# USB_keyholder.net
KiCad netlist of a schematic drawn in Altium Designer
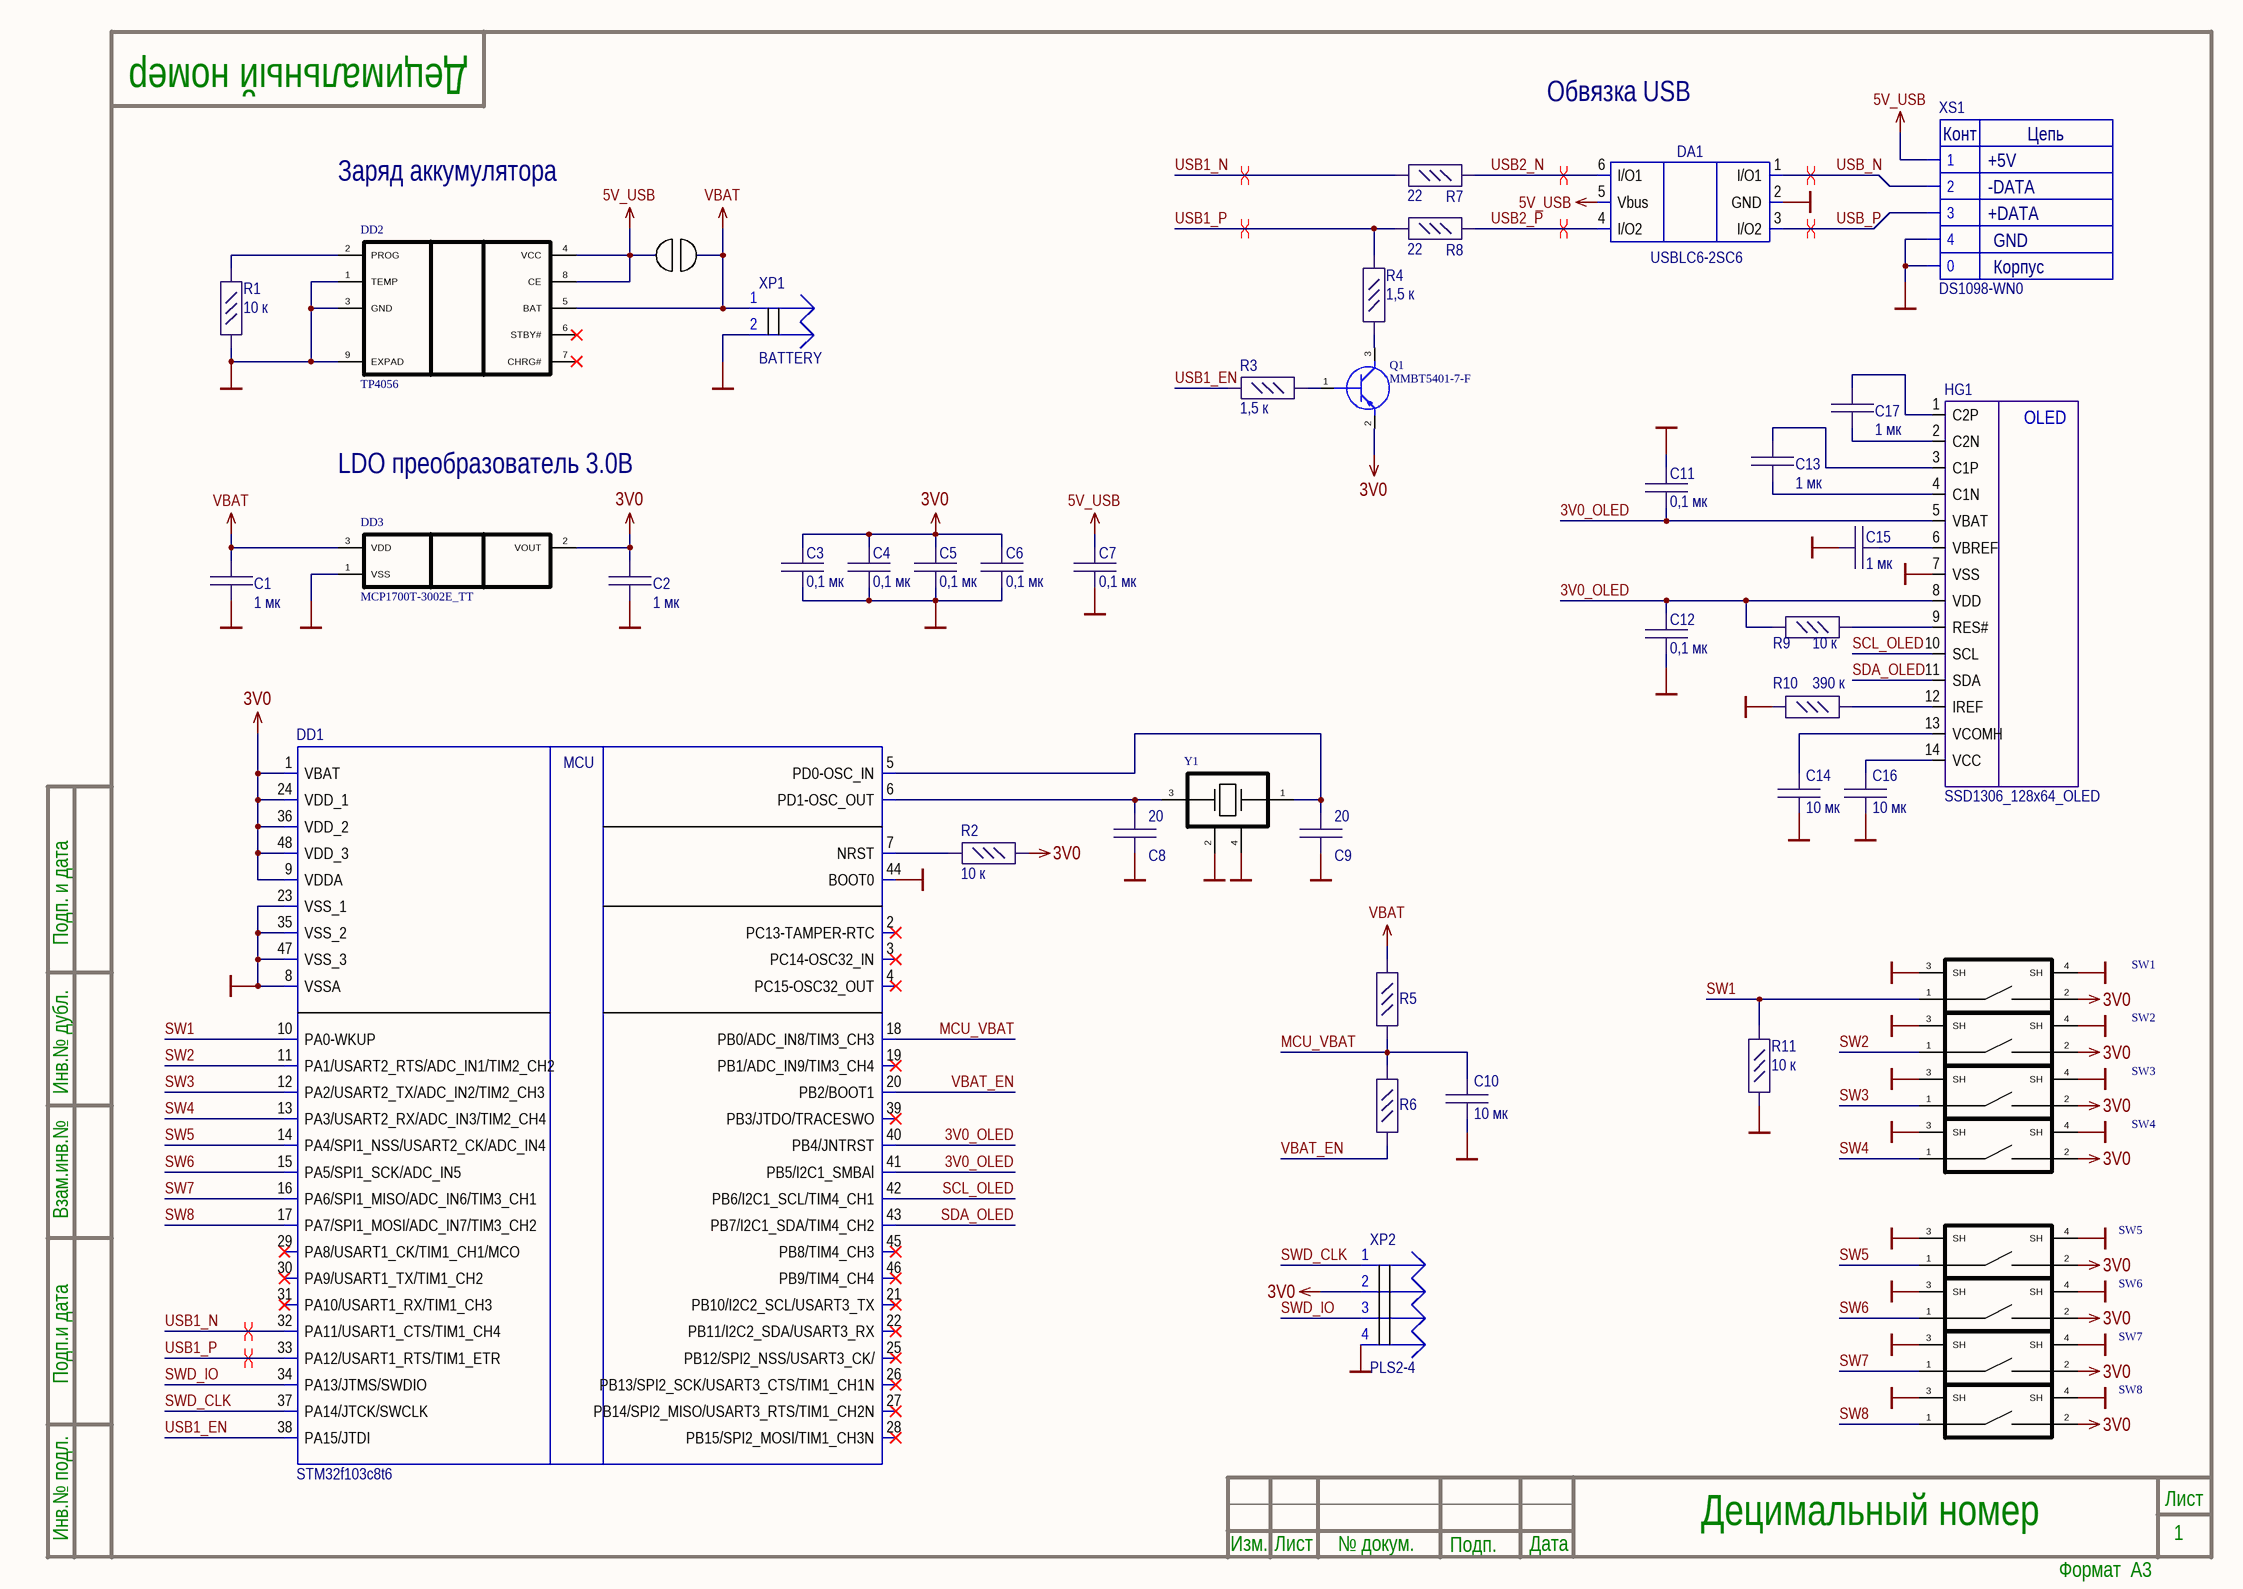
[diagram p0: USB_keyholder.SchDoc]

(export (version "E")
  (design (tool "Eeschema 10.0.6"))
  (components
    (comp (ref "C1")
      (value "1 мк")
      (footprint "C_0603")
      (description "CAP CER 2.2UF 25V X5R 0603")
      (fields
        (field (name "PART NUMBER") "GRM188R61E225MA12D")
        (field (name "MANUFACTURER") "Murata Electronics")
      )
      (libsource (lib "Database_Lib") (part "Capasitor"))
    )
    (comp (ref "C2")
      (value "1 мк")
      (footprint "C_0603")
      (description "CAP CER 2.2UF 25V X5R 0603")
      (fields
        (field (name "PART NUMBER") "GRM188R61E225MA12D")
        (field (name "MANUFACTURER") "Murata Electronics")
      )
      (libsource (lib "Database_Lib") (part "Capasitor"))
    )
    (comp (ref "C3")
      (value "0,1 мк")
      (footprint "C_0603")
      (description "CAP CER 0.1UF 100V X7R 0603")
      (fields
        (field (name "PART NUMBER") "GRM188R72A104MA35D")
        (field (name "MANUFACTURER") "Murata Electronics")
      )
      (libsource (lib "Database_Lib") (part "Capasitor"))
    )
    (comp (ref "C4")
      (value "0,1 мк")
      (footprint "C_0603")
      (description "CAP CER 0.1UF 100V X7R 0603")
      (fields
        (field (name "PART NUMBER") "GRM188R72A104MA35D")
        (field (name "MANUFACTURER") "Murata Electronics")
      )
      (libsource (lib "Database_Lib") (part "Capasitor"))
    )
    (comp (ref "C5")
      (value "0,1 мк")
      (footprint "C_0603")
      (description "CAP CER 0.1UF 100V X7R 0603")
      (fields
        (field (name "PART NUMBER") "GRM188R72A104MA35D")
        (field (name "MANUFACTURER") "Murata Electronics")
      )
      (libsource (lib "Database_Lib") (part "Capasitor"))
    )
    (comp (ref "C6")
      (value "0,1 мк")
      (footprint "C_0603")
      (description "CAP CER 0.1UF 100V X7R 0603")
      (fields
        (field (name "PART NUMBER") "GRM188R72A104MA35D")
        (field (name "MANUFACTURER") "Murata Electronics")
      )
      (libsource (lib "Database_Lib") (part "Capasitor"))
    )
    (comp (ref "C7")
      (value "0,1 мк")
      (footprint "C_0603")
      (description "CAP CER 0.1UF 100V X7R 0603")
      (fields
        (field (name "PART NUMBER") "GRM188R72A104MA35D")
        (field (name "MANUFACTURER") "Murata Electronics")
      )
      (libsource (lib "Database_Lib") (part "Capasitor"))
    )
    (comp (ref "C8")
      (value "20")
      (footprint "C_0603")
      (description "CAP CER 20PF 50V C0G/NP0 0603")
      (fields
        (field (name "PART NUMBER") "GRM1885C1H100FA01D")
        (field (name "MANUFACTURER") "Murata Electronics")
      )
      (libsource (lib "Database_Lib") (part "Capasitor"))
    )
    (comp (ref "C9")
      (value "20")
      (footprint "C_0603")
      (description "CAP CER 20PF 50V C0G/NP0 0603")
      (fields
        (field (name "PART NUMBER") "GRM1885C1H100FA01D")
        (field (name "MANUFACTURER") "Murata Electronics")
      )
      (libsource (lib "Database_Lib") (part "Capasitor"))
    )
    (comp (ref "C10")
      (value "10 мк")
      (footprint "C_0603")
      (description "CAP CER 10UF 10V X5R 0603")
      (fields
        (field (name "PART NUMBER") "GRM188R61A106KE69J")
        (field (name "MANUFACTURER") "Murata Electronics")
      )
      (libsource (lib "Database_Lib") (part "Capasitor"))
    )
    (comp (ref "C11")
      (value "0,1 мк")
      (footprint "C_0603")
      (description "CAP CER 0.1UF 100V X7R 0603")
      (fields
        (field (name "PART NUMBER") "GRM188R72A104MA35D")
        (field (name "MANUFACTURER") "Murata Electronics")
      )
      (libsource (lib "Database_Lib") (part "Capasitor"))
    )
    (comp (ref "C12")
      (value "0,1 мк")
      (footprint "C_0603")
      (description "CAP CER 0.1UF 100V X7R 0603")
      (fields
        (field (name "PART NUMBER") "GRM188R72A104MA35D")
        (field (name "MANUFACTURER") "Murata Electronics")
      )
      (libsource (lib "Database_Lib") (part "Capasitor"))
    )
    (comp (ref "C13")
      (value "1 мк")
      (footprint "C_0603")
      (description "CAP CER 2.2UF 25V X5R 0603")
      (fields
        (field (name "PART NUMBER") "GRM188R61E225MA12D")
        (field (name "MANUFACTURER") "Murata Electronics")
      )
      (libsource (lib "Database_Lib") (part "Capasitor"))
    )
    (comp (ref "C14")
      (value "10 мк")
      (footprint "C_0603")
      (description "CAP CER 10UF 10V X5R 0603")
      (fields
        (field (name "PART NUMBER") "GRM188R61A106KE69J")
        (field (name "MANUFACTURER") "Murata Electronics")
      )
      (libsource (lib "Database_Lib") (part "Capasitor"))
    )
    (comp (ref "C15")
      (value "1 мк")
      (footprint "C_0603")
      (description "CAP CER 2.2UF 25V X5R 0603")
      (fields
        (field (name "PART NUMBER") "GRM188R61E225MA12D")
        (field (name "MANUFACTURER") "Murata Electronics")
      )
      (libsource (lib "Database_Lib") (part "Capasitor"))
    )
    (comp (ref "C16")
      (value "10 мк")
      (footprint "C_0603")
      (description "CAP CER 10UF 10V X5R 0603")
      (fields
        (field (name "PART NUMBER") "GRM188R61A106KE69J")
        (field (name "MANUFACTURER") "Murata Electronics")
      )
      (libsource (lib "Database_Lib") (part "Capasitor"))
    )
    (comp (ref "C17")
      (value "1 мк")
      (footprint "C_0603")
      (description "CAP CER 2.2UF 25V X5R 0603")
      (fields
        (field (name "PART NUMBER") "GRM188R61E225MA12D")
        (field (name "MANUFACTURER") "Murata Electronics")
      )
      (libsource (lib "Database_Lib") (part "Capasitor"))
    )
    (comp (ref "DA1")
      (value "USBLC6-2SC6")
      (footprint "SOT-23-6")
      (libsource (lib "2. Chips") (part "USBLC6-2SC6"))
    )
    (comp (ref "DD1")
      (value "STM32f103c8t6")
      (footprint "LQFP48")
      (libsource (lib "6.Chips") (part "STM32f103c8t6"))
    )
    (comp (ref "DD2")
      (value "TP4056")
      (footprint "SOIC127P600X175-9N")
      (description "Li Ion charger")
      (fields (field (name "LCSC PART #") "C16581"))
      (libsource (lib "my-lib") (part "TP4056"))
    )
    (comp (ref "DD3")
      (value "MCP1700T-3002E_TT")
      (footprint "SOT95P237X112-3N")
      (fields (field (name "LCSC PART #") "C62244"))
      (libsource (lib "my-lib") (part "MCP1700T-3002E_TT"))
    )
    (comp (ref "HG1")
      (value "SSD1306_128х64_OLED")
      (footprint "14_pin_OLED")
      (libsource (lib "11.Other") (part "SSD1306_128х64_OLED"))
    )
    (comp (ref "Q1")
      (value "MMBT5401-7-F")
      (footprint "SamacSys:SOT95P240X120-3N")
      (description "Transistor BJT PNP")
      (fields (field (name "MOUSER PART NUMBER") "621-MMBT5401-F") (field (name "LCSC PART #") "C8326"))
      (libsource (lib "*") (part "MMBT5401-7-F"))
    )
    (comp (ref "R1")
      (value "10 к")
      (footprint "R_0603")
      (description "RES SMD 10K OHM 1% 1/10W 0603")
      (fields (field (name "PART NUMBER") "CR0603-FX-1002ELF") (field (name "MANUFACTURER") "Bourns Inc."))
      (libsource (lib "Database_Lib") (part "Resistor"))
    )
    (comp (ref "R2")
      (value "10 к")
      (footprint "R_0603")
      (description "RES SMD 10K OHM 1% 1/10W 0603")
      (fields (field (name "PART NUMBER") "CR0603-FX-1002ELF") (field (name "MANUFACTURER") "Bourns Inc."))
      (libsource (lib "Database_Lib") (part "Resistor"))
    )
    (comp (ref "R3")
      (value "1,5 к")
      (footprint "R_0603")
      (description "RES SMD 1.5K OHM 1% 1/10W 0603")
      (fields (field (name "PART NUMBER") "CR0603-FX-1501ELF") (field (name "MANUFACTURER") "Bourns Inc."))
      (libsource (lib "Database_Lib") (part "Resistor"))
    )
    (comp (ref "R4")
      (value "1,5 к")
      (footprint "R_0603")
      (description "RES SMD 1.5K OHM 1% 1/10W 0603")
      (fields (field (name "PART NUMBER") "CR0603-FX-1501ELF") (field (name "MANUFACTURER") "Bourns Inc."))
      (libsource (lib "Database_Lib") (part "Resistor"))
    )
    (comp (ref "R5")
      (value "1 M")
      (footprint "R_0603")
      (description "RES SMD 1M OHM 1% 1/10W 0603")
      (fields (field (name "PART NUMBER") "CR0603-FX-1004ELF") (field (name "MANUFACTURER") "Bourns Inc."))
      (libsource (lib "Database_Lib") (part "Resistor"))
    )
    (comp (ref "R6")
      (value "1 M")
      (footprint "R_0603")
      (description "RES SMD 1M OHM 1% 1/10W 0603")
      (fields (field (name "PART NUMBER") "CR0603-FX-1004ELF") (field (name "MANUFACTURER") "Bourns Inc."))
      (libsource (lib "Database_Lib") (part "Resistor"))
    )
    (comp (ref "R7")
      (value "22")
      (footprint "R_0603")
      (description "RES SMD 22 OHM 1% 1/10W 0603")
      (fields (field (name "PART NUMBER") "CR0603-FX-22R0ELF") (field (name "MANUFACTURER") "Bourns Inc."))
      (libsource (lib "Database_Lib") (part "Resistor"))
    )
    (comp (ref "R8")
      (value "22")
      (footprint "R_0603")
      (description "RES SMD 22 OHM 1% 1/10W 0603")
      (fields (field (name "PART NUMBER") "CR0603-FX-22R0ELF") (field (name "MANUFACTURER") "Bourns Inc."))
      (libsource (lib "Database_Lib") (part "Resistor"))
    )
    (comp (ref "R9")
      (value "10 к")
      (footprint "R_0603")
      (description "RES SMD 10K OHM 1% 1/10W 0603")
      (fields (field (name "PART NUMBER") "CR0603-FX-1002ELF") (field (name "MANUFACTURER") "Bourns Inc."))
      (libsource (lib "Database_Lib") (part "Resistor"))
    )
    (comp (ref "R10")
      (value "390 к")
      (footprint "R_0603")
      (description "RES SMD 390K OHM 1% 1/10W 0603")
      (fields (field (name "PART NUMBER") "CR0603-FX-3903ELF") (field (name "MANUFACTURER") "Bourns Inc."))
      (libsource (lib "Database_Lib") (part "Resistor"))
    )
    (comp (ref "R11")
      (value "10 к")
      (footprint "R_0603")
      (description "RES SMD 10K OHM 1% 1/10W 0603")
      (fields (field (name "PART NUMBER") "CR0603-FX-1002ELF") (field (name "MANUFACTURER") "Bourns Inc."))
      (libsource (lib "Database_Lib") (part "Resistor"))
    )
    (comp (ref "SW1")
      (value "TSA365G00D")
      (footprint "1TS002G26003500CT")
      (libsource (lib "my-lib") (part "TSA365G00D"))
    )
    (comp (ref "SW2")
      (value "TSA365G00D")
      (footprint "1TS002G26003500CT")
      (libsource (lib "my-lib") (part "TSA365G00D"))
    )
    (comp (ref "SW3")
      (value "TSA365G00D")
      (footprint "1TS002G26003500CT")
      (libsource (lib "my-lib") (part "TSA365G00D"))
    )
    (comp (ref "SW4")
      (value "TSA365G00D")
      (footprint "1TS002G26003500CT")
      (libsource (lib "my-lib") (part "TSA365G00D"))
    )
    (comp (ref "SW5")
      (value "TSA365G00D")
      (footprint "1TS002G26003500CT")
      (libsource (lib "my-lib") (part "TSA365G00D"))
    )
    (comp (ref "SW6")
      (value "TSA365G00D")
      (footprint "1TS002G26003500CT")
      (libsource (lib "my-lib") (part "TSA365G00D"))
    )
    (comp (ref "SW7")
      (value "TSA365G00D")
      (footprint "1TS002G26003500CT")
      (libsource (lib "my-lib") (part "TSA365G00D"))
    )
    (comp (ref "SW8")
      (value "TSA365G00D")
      (footprint "1TS002G26003500CT")
      (libsource (lib "my-lib") (part "TSA365G00D"))
    )
    (comp (ref "X1")
      (value "Solder_jumper")
      (footprint "Solder_jumper")
      (libsource (lib "11.Other") (part "Solder_jumper"))
    )
    (comp (ref "XP1") (value "BATTERY") (footprint "PLS-2") (libsource (lib "7.Connectors") (part "PLS-2")))
    (comp (ref "XP2")
      (value "PLS2-4")
      (footprint "4 pin debug")
      (libsource (lib "7.Connectors") (part "PLS2-4"))
    )
    (comp (ref "XS1")
      (value "DS1098-WN0")
      (footprint "DS1098-WN0")
      (libsource (lib "7.Connectors") (part "DS1098-WN0"))
    )
    (comp (ref "Y1")
      (value "X322512MSB4SI")
      (footprint "X322512MSB4SI")
      (description "12MHz Crystal resonator")
      (fields (field (name "LCSC PART #") "C9002"))
      (libsource (lib "my-lib") (part "X322512MSB4SI"))
    )
  )
  (nets
    (net (code "1") (name "/3V0_OLED") (class "Default")
      (node (ref "C11") (pin "1") (pinfunction "1_1") (pintype "passive"))
      (node (ref "C12") (pin "2") (pinfunction "2_2") (pintype "passive"))
      (node (ref "DD1") (pin "40") (pinfunction "PB4/JNTRST_40") (pintype "passive"))
      (node (ref "DD1") (pin "41") (pinfunction "PB5/I2C1_SMBAl_41") (pintype "passive"))
      (node (ref "HG1") (pin "5") (pinfunction "VBAT_5") (pintype "passive"))
      (node (ref "HG1") (pin "8") (pinfunction "VDD_8") (pintype "passive"))
      (node (ref "R9") (pin "2") (pinfunction "2_2") (pintype "passive"))
    )
    (net (code "2") (name "/MCU_VBAT") (class "Default")
      (node (ref "C10") (pin "2") (pinfunction "2_2") (pintype "passive"))
      (node (ref "DD1") (pin "18") (pinfunction "PB0/ADC_IN8/TIM3_CH3_18") (pintype "passive"))
      (node (ref "R5") (pin "1") (pinfunction "1_1") (pintype "passive"))
      (node (ref "R6") (pin "2") (pinfunction "2_2") (pintype "passive"))
    )
    (net (code "3") (name "/SCL_OLED") (class "Default")
      (node (ref "DD1") (pin "42") (pinfunction "PB6/I2C1_SCL/TIM4_CH1_42") (pintype "passive"))
      (node (ref "HG1") (pin "10") (pinfunction "SCL_10") (pintype "passive"))
    )
    (net (code "4") (name "/SDA_OLED") (class "Default")
      (node (ref "DD1") (pin "43") (pinfunction "PB7/I2C1_SDA/TIM4_CH2_43") (pintype "passive"))
      (node (ref "HG1") (pin "11") (pinfunction "SDA_11") (pintype "passive"))
    )
    (net (code "5") (name "/SW1") (class "Default")
      (node (ref "DD1") (pin "10") (pinfunction "PA0-WKUP_10") (pintype "passive"))
      (node (ref "R11") (pin "2") (pinfunction "2_2") (pintype "passive"))
      (node (ref "SW1") (pin "1") (pinfunction "VSS_1") (pintype "power_in"))
    )
    (net (code "6") (name "/SW2") (class "Default")
      (node (ref "DD1") (pin "11") (pinfunction "PA1/USART2_RTS/ADC_IN1/TIM2_CH2_11") (pintype "passive"))
      (node (ref "SW2") (pin "1") (pinfunction "VSS_1") (pintype "power_in"))
    )
    (net (code "7") (name "/SW3") (class "Default")
      (node (ref "DD1") (pin "12") (pinfunction "PA2/USART2_TX/ADC_IN2/TIM2_CH3_12") (pintype "passive"))
      (node (ref "SW3") (pin "1") (pinfunction "VSS_1") (pintype "power_in"))
    )
    (net (code "8") (name "/SW4") (class "Default")
      (node (ref "DD1") (pin "13") (pinfunction "PA3/USART2_RX/ADC_IN3/TIM2_CH4_13") (pintype "passive"))
      (node (ref "SW4") (pin "1") (pinfunction "VSS_1") (pintype "power_in"))
    )
    (net (code "9") (name "/SW5") (class "Default")
      (node (ref "DD1") (pin "14") (pinfunction "PA4/SPI1_NSS/USART2_CK/ADC_IN4_14") (pintype "passive"))
      (node (ref "SW5") (pin "1") (pinfunction "VSS_1") (pintype "power_in"))
    )
    (net (code "10") (name "/SW6") (class "Default")
      (node (ref "DD1") (pin "15") (pinfunction "PA5/SPI1_SCK/ADC_IN5_15") (pintype "passive"))
      (node (ref "SW6") (pin "1") (pinfunction "VSS_1") (pintype "power_in"))
    )
    (net (code "11") (name "/SW7") (class "Default")
      (node (ref "DD1") (pin "16") (pinfunction "PA6/SPI1_MISO/ADC_IN6/TIM3_CH1_16") (pintype "passive"))
      (node (ref "SW7") (pin "1") (pinfunction "VSS_1") (pintype "power_in"))
    )
    (net (code "12") (name "/SW8") (class "Default")
      (node (ref "DD1") (pin "17") (pinfunction "PA7/SPI1_MOSI/ADC_IN7/TIM3_CH2_17") (pintype "passive"))
      (node (ref "SW8") (pin "1") (pinfunction "VSS_1") (pintype "power_in"))
    )
    (net (code "13") (name "/SWD_CLK") (class "Default")
      (node (ref "DD1") (pin "37") (pinfunction "PA14/JTCK/SWCLK_37") (pintype "passive"))
      (node (ref "XP2") (pin "1") (pinfunction "1_1") (pintype "passive"))
    )
    (net (code "14") (name "/SWD_IO") (class "Default")
      (node (ref "DD1") (pin "34") (pinfunction "PA13/JTMS/SWDIO_34") (pintype "passive"))
      (node (ref "XP2") (pin "3") (pinfunction "3_3") (pintype "passive"))
    )
    (net (code "15") (name "/USB1_EN") (class "Default")
      (node (ref "DD1") (pin "38") (pinfunction "PA15/JTDI_38") (pintype "passive"))
      (node (ref "R3") (pin "2") (pinfunction "2_2") (pintype "passive"))
    )
    (net (code "16") (name "/USB1_N") (class "Default")
      (node (ref "DD1") (pin "32") (pinfunction "PA11/USART1_CTS/TIM1_CH4_32") (pintype "passive"))
      (node (ref "R7") (pin "1") (pinfunction "1_1") (pintype "passive"))
    )
    (net (code "17") (name "/USB1_P") (class "Default")
      (node (ref "DD1") (pin "33") (pinfunction "PA12/USART1_RTS/TIM1_ETR_33") (pintype "passive"))
      (node (ref "R4") (pin "2") (pinfunction "2_2") (pintype "passive"))
      (node (ref "R8") (pin "1") (pinfunction "1_1") (pintype "passive"))
    )
    (net (code "18") (name "/USB2_N") (class "Default")
      (node (ref "DA1") (pin "6") (pinfunction "I/O1_6") (pintype "passive"))
      (node (ref "R7") (pin "2") (pinfunction "2_2") (pintype "passive"))
    )
    (net (code "19") (name "/USB2_P") (class "Default")
      (node (ref "DA1") (pin "4") (pinfunction "I/O2_4") (pintype "passive"))
      (node (ref "R8") (pin "2") (pinfunction "2_2") (pintype "passive"))
    )
    (net (code "20") (name "/USB_N") (class "Default")
      (node (ref "DA1") (pin "1") (pinfunction "I/O1_1") (pintype "passive"))
      (node (ref "XS1") (pin "2") (pinfunction "2_2") (pintype "passive"))
    )
    (net (code "21") (name "/USB_P") (class "Default")
      (node (ref "DA1") (pin "3") (pinfunction "I/O2_3") (pintype "passive"))
      (node (ref "XS1") (pin "3") (pinfunction "3_3") (pintype "passive"))
    )
    (net (code "22") (name "/VBAT_EN") (class "Default")
      (node (ref "DD1") (pin "20") (pinfunction "PB2/BOOT1_20") (pintype "passive"))
      (node (ref "R6") (pin "1") (pinfunction "1_1") (pintype "passive"))
    )
    (net (code "23") (name "3V0") (class "Default")
      (node (ref "C2") (pin "2") (pinfunction "2_2") (pintype "passive"))
      (node (ref "C3") (pin "2") (pinfunction "2_2") (pintype "passive"))
      (node (ref "C4") (pin "2") (pinfunction "2_2") (pintype "passive"))
      (node (ref "C5") (pin "2") (pinfunction "2_2") (pintype "passive"))
      (node (ref "C6") (pin "2") (pinfunction "2_2") (pintype "passive"))
      (node (ref "DD1") (pin "1") (pinfunction "VBAT_1") (pintype "passive"))
      (node (ref "DD1") (pin "24") (pinfunction "VDD_1_24") (pintype "passive"))
      (node (ref "DD1") (pin "36") (pinfunction "VDD_2_36") (pintype "passive"))
      (node (ref "DD1") (pin "48") (pinfunction "VDD_3_48") (pintype "passive"))
      (node (ref "DD1") (pin "9") (pinfunction "VDDA_9") (pintype "passive"))
      (node (ref "DD3") (pin "2") (pinfunction "VOUT_2") (pintype "passive"))
      (node (ref "Q1") (pin "2") (pinfunction "E_2") (pintype "passive"))
      (node (ref "R2") (pin "1") (pinfunction "1_1") (pintype "passive"))
      (node (ref "SW1") (pin "2") (pinfunction "VOUT_2") (pintype "passive"))
      (node (ref "SW2") (pin "2") (pinfunction "VOUT_2") (pintype "passive"))
      (node (ref "SW3") (pin "2") (pinfunction "VOUT_2") (pintype "passive"))
      (node (ref "SW4") (pin "2") (pinfunction "VOUT_2") (pintype "passive"))
      (node (ref "SW5") (pin "2") (pinfunction "VOUT_2") (pintype "passive"))
      (node (ref "SW6") (pin "2") (pinfunction "VOUT_2") (pintype "passive"))
      (node (ref "SW7") (pin "2") (pinfunction "VOUT_2") (pintype "passive"))
      (node (ref "SW8") (pin "2") (pinfunction "VOUT_2") (pintype "passive"))
      (node (ref "XP2") (pin "2") (pinfunction "2_2") (pintype "passive"))
    )
    (net (code "24") (name "5V_USB") (class "Default")
      (node (ref "C7") (pin "2") (pinfunction "2_2") (pintype "passive"))
      (node (ref "DA1") (pin "5") (pinfunction "Vbus_5") (pintype "passive"))
      (node (ref "DD2") (pin "4") (pinfunction "VCC_4") (pintype "passive"))
      (node (ref "DD2") (pin "8") (pinfunction "CE_8") (pintype "power_in"))
      (node (ref "X1") (pin "1") (pinfunction "1_1") (pintype "passive"))
      (node (ref "XS1") (pin "1") (pinfunction "1_1") (pintype "passive"))
    )
    (net (code "25") (name "GND") (class "Default")
      (node (ref "C1") (pin "1") (pinfunction "1_1") (pintype "passive"))
      (node (ref "C10") (pin "1") (pinfunction "1_1") (pintype "passive"))
      (node (ref "C11") (pin "2") (pinfunction "2_2") (pintype "passive"))
      (node (ref "C12") (pin "1") (pinfunction "1_1") (pintype "passive"))
      (node (ref "C14") (pin "1") (pinfunction "1_1") (pintype "passive"))
      (node (ref "C15") (pin "2") (pinfunction "2_2") (pintype "passive"))
      (node (ref "C16") (pin "1") (pinfunction "1_1") (pintype "passive"))
      (node (ref "C2") (pin "1") (pinfunction "1_1") (pintype "passive"))
      (node (ref "C3") (pin "1") (pinfunction "1_1") (pintype "passive"))
      (node (ref "C4") (pin "1") (pinfunction "1_1") (pintype "passive"))
      (node (ref "C5") (pin "1") (pinfunction "1_1") (pintype "passive"))
      (node (ref "C6") (pin "1") (pinfunction "1_1") (pintype "passive"))
      (node (ref "C7") (pin "1") (pinfunction "1_1") (pintype "passive"))
      (node (ref "C8") (pin "1") (pinfunction "1_1") (pintype "passive"))
      (node (ref "C9") (pin "1") (pinfunction "1_1") (pintype "passive"))
      (node (ref "DA1") (pin "2") (pinfunction "GND_2") (pintype "passive"))
      (node (ref "DD1") (pin "23") (pinfunction "VSS_1_23") (pintype "passive"))
      (node (ref "DD1") (pin "35") (pinfunction "VSS_2_35") (pintype "passive"))
      (node (ref "DD1") (pin "44") (pinfunction "BOOT0_44") (pintype "passive"))
      (node (ref "DD1") (pin "47") (pinfunction "VSS_3_47") (pintype "passive"))
      (node (ref "DD1") (pin "8") (pinfunction "VSSA_8") (pintype "passive"))
      (node (ref "DD2") (pin "1") (pinfunction "TEMP_1") (pintype "passive"))
      (node (ref "DD2") (pin "3") (pinfunction "GND_3") (pintype "power_in"))
      (node (ref "DD2") (pin "9") (pinfunction "EXPAD_9") (pintype "power_in"))
      (node (ref "DD3") (pin "1") (pinfunction "VSS_1") (pintype "power_in"))
      (node (ref "HG1") (pin "7") (pinfunction "VSS_7") (pintype "passive"))
      (node (ref "R1") (pin "1") (pinfunction "1_1") (pintype "passive"))
      (node (ref "R10") (pin "1") (pinfunction "1_1") (pintype "passive"))
      (node (ref "R11") (pin "1") (pinfunction "1_1") (pintype "passive"))
      (node (ref "SW1") (pin "3") (pinfunction "SH_3") (pintype "passive"))
      (node (ref "SW1") (pin "4") (pinfunction "SH_4") (pintype "passive"))
      (node (ref "SW2") (pin "3") (pinfunction "SH_3") (pintype "passive"))
      (node (ref "SW2") (pin "4") (pinfunction "SH_4") (pintype "passive"))
      (node (ref "SW3") (pin "3") (pinfunction "SH_3") (pintype "passive"))
      (node (ref "SW3") (pin "4") (pinfunction "SH_4") (pintype "passive"))
      (node (ref "SW4") (pin "3") (pinfunction "SH_3") (pintype "passive"))
      (node (ref "SW4") (pin "4") (pinfunction "SH_4") (pintype "passive"))
      (node (ref "SW5") (pin "3") (pinfunction "SH_3") (pintype "passive"))
      (node (ref "SW5") (pin "4") (pinfunction "SH_4") (pintype "passive"))
      (node (ref "SW6") (pin "3") (pinfunction "SH_3") (pintype "passive"))
      (node (ref "SW6") (pin "4") (pinfunction "SH_4") (pintype "passive"))
      (node (ref "SW7") (pin "3") (pinfunction "SH_3") (pintype "passive"))
      (node (ref "SW7") (pin "4") (pinfunction "SH_4") (pintype "passive"))
      (node (ref "SW8") (pin "3") (pinfunction "SH_3") (pintype "passive"))
      (node (ref "SW8") (pin "4") (pinfunction "SH_4") (pintype "passive"))
      (node (ref "XP1") (pin "2") (pinfunction "2_2") (pintype "passive"))
      (node (ref "XP2") (pin "4") (pinfunction "4_4") (pintype "passive"))
      (node (ref "XS1") (pin "0") (pinfunction "0_0") (pintype "passive"))
      (node (ref "XS1") (pin "4") (pinfunction "4_4") (pintype "passive"))
      (node (ref "Y1") (pin "2") (pinfunction "2_2") (pintype "passive"))
      (node (ref "Y1") (pin "4") (pinfunction "4_4") (pintype "passive"))
    )
    (net (code "26") (name "Net-(DD1-NRST)") (class "Default")
      (node (ref "DD1") (pin "7") (pinfunction "NRST_7") (pintype "passive"))
      (node (ref "R2") (pin "2") (pinfunction "2_2") (pintype "passive"))
    )
    (net (code "27") (name "Net-(DD1-PD0-OSC_IN)") (class "Default")
      (node (ref "C9") (pin "2") (pinfunction "2_2") (pintype "passive"))
      (node (ref "DD1") (pin "5") (pinfunction "PD0-OSC_IN_5") (pintype "passive"))
      (node (ref "Y1") (pin "1") (pinfunction "3_1") (pintype "passive"))
    )
    (net (code "28") (name "Net-(DD1-PD1-OSC_OUT)") (class "Default")
      (node (ref "C8") (pin "2") (pinfunction "2_2") (pintype "passive"))
      (node (ref "DD1") (pin "6") (pinfunction "PD1-OSC_OUT_6") (pintype "passive"))
      (node (ref "Y1") (pin "3") (pinfunction "3_3") (pintype "passive"))
    )
    (net (code "29") (name "Net-(DD2-PROG)") (class "Default")
      (node (ref "DD2") (pin "2") (pinfunction "PROG_2") (pintype "passive"))
      (node (ref "R1") (pin "2") (pinfunction "2_2") (pintype "passive"))
    )
    (net (code "30") (name "Net-(HG1-C1N)") (class "Default")
      (node (ref "C13") (pin "1") (pinfunction "1_1") (pintype "passive"))
      (node (ref "HG1") (pin "4") (pinfunction "C1N_4") (pintype "passive"))
    )
    (net (code "31") (name "Net-(HG1-C1P)") (class "Default")
      (node (ref "C13") (pin "2") (pinfunction "2_2") (pintype "passive"))
      (node (ref "HG1") (pin "3") (pinfunction "C1P_3") (pintype "passive"))
    )
    (net (code "32") (name "Net-(HG1-C2N)") (class "Default")
      (node (ref "C17") (pin "1") (pinfunction "1_1") (pintype "passive"))
      (node (ref "HG1") (pin "2") (pinfunction "C2N_2") (pintype "passive"))
    )
    (net (code "33") (name "Net-(HG1-C2P)") (class "Default")
      (node (ref "C17") (pin "2") (pinfunction "2_2") (pintype "passive"))
      (node (ref "HG1") (pin "1") (pinfunction "C2P_1") (pintype "passive"))
    )
    (net (code "34") (name "Net-(HG1-IREF)") (class "Default")
      (node (ref "HG1") (pin "12") (pinfunction "IREF_12") (pintype "passive"))
      (node (ref "R10") (pin "2") (pinfunction "2_2") (pintype "passive"))
    )
    (net (code "35") (name "Net-(HG1-RES#)") (class "Default")
      (node (ref "HG1") (pin "9") (pinfunction "RES#_9") (pintype "passive"))
      (node (ref "R9") (pin "1") (pinfunction "1_1") (pintype "passive"))
    )
    (net (code "36") (name "Net-(HG1-VBREF)") (class "Default")
      (node (ref "C15") (pin "1") (pinfunction "1_1") (pintype "passive"))
      (node (ref "HG1") (pin "6") (pinfunction "VBREF_6") (pintype "passive"))
    )
    (net (code "37") (name "Net-(HG1-VCC)") (class "Default")
      (node (ref "C16") (pin "2") (pinfunction "2_2") (pintype "passive"))
      (node (ref "HG1") (pin "14") (pinfunction "VCC_14") (pintype "passive"))
    )
    (net (code "38") (name "Net-(HG1-VCOMH)") (class "Default")
      (node (ref "C14") (pin "2") (pinfunction "2_2") (pintype "passive"))
      (node (ref "HG1") (pin "13") (pinfunction "VCOMH_13") (pintype "passive"))
    )
    (net (code "39") (name "Net-(Q1-B)") (class "Default")
      (node (ref "Q1") (pin "1") (pinfunction "B_1") (pintype "passive"))
      (node (ref "R3") (pin "1") (pinfunction "1_1") (pintype "passive"))
    )
    (net (code "40") (name "Net-(Q1-C)") (class "Default")
      (node (ref "Q1") (pin "3") (pinfunction "C_3") (pintype "passive"))
      (node (ref "R4") (pin "1") (pinfunction "1_1") (pintype "passive"))
    )
    (net (code "41") (name "VBAT") (class "Default")
      (node (ref "C1") (pin "2") (pinfunction "2_2") (pintype "passive"))
      (node (ref "DD2") (pin "5") (pinfunction "BAT_5") (pintype "passive"))
      (node (ref "DD3") (pin "3") (pinfunction "VDD_3") (pintype "passive"))
      (node (ref "R5") (pin "2") (pinfunction "2_2") (pintype "passive"))
      (node (ref "X1") (pin "2") (pinfunction "2_2") (pintype "passive"))
      (node (ref "XP1") (pin "1") (pinfunction "1_1") (pintype "passive"))
    )
    (net (code "42") (name "unconnected-(DD1-PA8{slash}USART1_CK{slash}TIM1_CH1{slash}MCO-Pad29)") (class "Default")
      (node (ref "DD1") (pin "29") (pinfunction "PA8/USART1_CK/TIM1_CH1/MCO_29") (pintype "passive+no_connect"))
    )
    (net (code "43") (name "unconnected-(DD1-PA9{slash}USART1_TX{slash}TIM1_CH2-Pad30)") (class "Default")
      (node (ref "DD1") (pin "30") (pinfunction "PA9/USART1_TX/TIM1_CH2_30") (pintype "passive+no_connect"))
    )
    (net (code "44") (name "unconnected-(DD1-PA10{slash}USART1_RX{slash}TIM1_CH3-Pad31)") (class "Default")
      (node (ref "DD1") (pin "31") (pinfunction "PA10/USART1_RX/TIM1_CH3_31") (pintype "passive+no_connect"))
    )
    (net (code "45") (name "unconnected-(DD1-PB1{slash}ADC_IN9{slash}TIM3_CH4-Pad19)") (class "Default")
      (node (ref "DD1") (pin "19") (pinfunction "PB1/ADC_IN9/TIM3_CH4_19") (pintype "passive+no_connect"))
    )
    (net (code "46") (name "unconnected-(DD1-PB3{slash}JTDO{slash}TRACESWO-Pad39)") (class "Default")
      (node (ref "DD1") (pin "39") (pinfunction "PB3/JTDO/TRACESWO_39") (pintype "passive+no_connect"))
    )
    (net (code "47") (name "unconnected-(DD1-PB8{slash}TIM4_CH3-Pad45)") (class "Default")
      (node (ref "DD1") (pin "45") (pinfunction "PB8/TIM4_CH3_45") (pintype "passive+no_connect"))
    )
    (net (code "48") (name "unconnected-(DD1-PB9{slash}TIM4_CH4-Pad46)") (class "Default")
      (node (ref "DD1") (pin "46") (pinfunction "PB9/TIM4_CH4_46") (pintype "passive+no_connect"))
    )
    (net (code "49") (name "unconnected-(DD1-PB10{slash}I2C2_SCL{slash}USART3_TX-Pad21)") (class "Default")
      (node (ref "DD1") (pin "21") (pinfunction "PB10/I2C2_SCL/USART3_TX_21") (pintype "passive+no_connect"))
    )
    (net (code "50") (name "unconnected-(DD1-PB11{slash}I2C2_SDA{slash}USART3_RX-Pad22)") (class "Default")
      (node (ref "DD1") (pin "22") (pinfunction "PB11/I2C2_SDA/USART3_RX_22") (pintype "passive+no_connect"))
    )
    (net (code "51") (name "unconnected-(DD1-PB12{slash}SPI2_NSS{slash}USART3_CK{slash}-Pad25)") (class "Default")
      (node (ref "DD1") (pin "25") (pinfunction "PB12/SPI2_NSS/USART3_CK/_25") (pintype "passive+no_connect"))
    )
    (net (code "52") (name "unconnected-(DD1-PB13{slash}SPI2_SCK{slash}USART3_CTS{slash}TIM1_CH1N-Pad26)") (class "Default")
      (node (ref "DD1") (pin "26") (pinfunction "PB13/SPI2_SCK/USART3_CTS/TIM1_CH1N_26") (pintype "passive+no_connect"))
    )
    (net (code "53") (name "unconnected-(DD1-PB14{slash}SPI2_MISO{slash}USART3_RTS{slash}TIM1_CH2N-Pad27)") (class "Default")
      (node (ref "DD1") (pin "27") (pinfunction "PB14/SPI2_MISO/USART3_RTS/TIM1_CH2N_27") (pintype "passive+no_connect"))
    )
    (net (code "54") (name "unconnected-(DD1-PB15{slash}SPI2_MOSI{slash}TIM1_CH3N-Pad28)") (class "Default")
      (node (ref "DD1") (pin "28") (pinfunction "PB15/SPI2_MOSI/TIM1_CH3N_28") (pintype "passive+no_connect"))
    )
    (net (code "55") (name "unconnected-(DD1-PC13-TAMPER-RTC-Pad2)") (class "Default")
      (node (ref "DD1") (pin "2") (pinfunction "PC13-TAMPER-RTC_2") (pintype "passive+no_connect"))
    )
    (net (code "56") (name "unconnected-(DD1-PC14-OSC32_IN-Pad3)") (class "Default")
      (node (ref "DD1") (pin "3") (pinfunction "PC14-OSC32_IN_3") (pintype "passive+no_connect"))
    )
    (net (code "57") (name "unconnected-(DD1-PC15-OSC32_OUT-Pad4)") (class "Default")
      (node (ref "DD1") (pin "4") (pinfunction "PC15-OSC32_OUT_4") (pintype "passive+no_connect"))
    )
    (net (code "58") (name "unconnected-(DD2-CHRG#-Pad7)") (class "Default")
      (node (ref "DD2") (pin "7") (pinfunction "CHRG#_7") (pintype "passive+no_connect"))
    )
    (net (code "59") (name "unconnected-(DD2-STBY#-Pad6)") (class "Default")
      (node (ref "DD2") (pin "6") (pinfunction "STBY#_6") (pintype "passive+no_connect"))
    )
  )
)
